# Lemming2_power.net
KiCad netlist of a schematic drawn in EAGLE
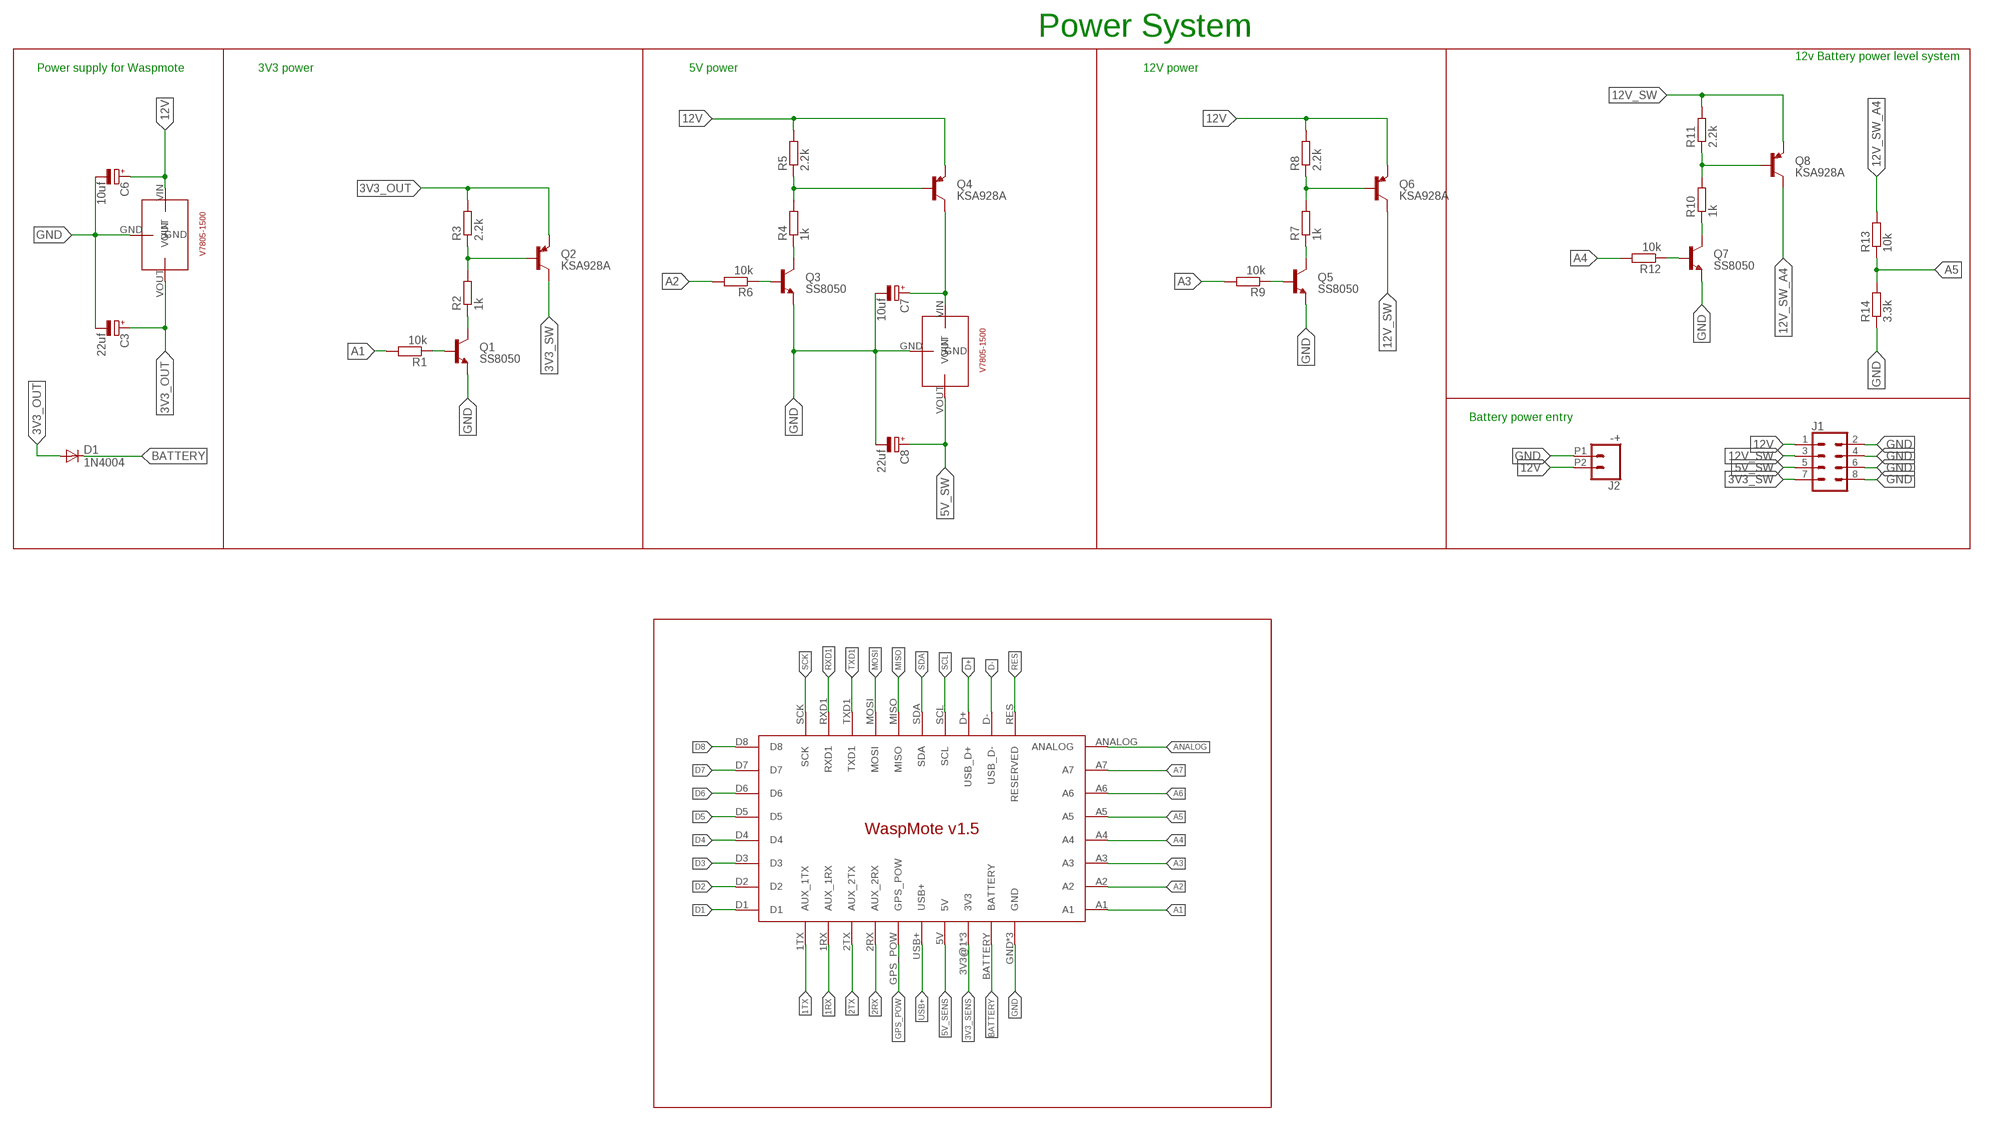
[diagram p0: schematic, sheet 1]

(export (version "E")
  (design (tool "Eeschema 10.0.6"))
  (components
    (comp (ref "C3")
      (value "22uf")
      (footprint "eagle-import:E2,5-5")
      (libsource (lib "eagle-import") (part "CPOL-EUE2.5-5"))
    )
    (comp (ref "C6")
      (value "10uf")
      (footprint "eagle-import:E2,5-5")
      (libsource (lib "eagle-import") (part "CPOL-EUE2.5-5"))
    )
    (comp (ref "C7")
      (value "10uf")
      (footprint "eagle-import:E2,5-5")
      (libsource (lib "eagle-import") (part "CPOL-EUE2.5-5"))
    )
    (comp (ref "C8")
      (value "22uf")
      (footprint "eagle-import:E2,5-5")
      (libsource (lib "eagle-import") (part "CPOL-EUE2.5-5"))
    )
    (comp (ref "D1")
      (value "1N4004")
      (footprint "eagle-import:DO41-10")
      (libsource (lib "eagle-import") (part "1N4004"))
    )
    (comp (ref "J1")
      (value "CONN_04X2")
      (footprint "eagle-import:2X4")
      (libsource (lib "eagle-import") (part "CONN_04X2"))
    )
    (comp (ref "J2")
      (value "-+")
      (footprint "eagle-import:1X02_2.54_SCREWTERM")
      (libsource (lib "eagle-import") (part "CONN_022.54MM_SCREWTERM"))
    )
    (comp (ref "LM7805")
      (value "V7805-1500")
      (footprint "eagle-import:V7805-1500")
      (libsource (lib "eagle-import") (part "V7805-1500"))
    )
    (comp (ref "Q1")
      (value "SS8050")
      (footprint "eagle-import:TO-92-EBC")
      (libsource (lib "eagle-import") (part "SS8050"))
    )
    (comp (ref "Q2")
      (value "KSA928A")
      (footprint "eagle-import:TO-92-ECB")
      (libsource (lib "eagle-import") (part "KSA928A"))
    )
    (comp (ref "Q3")
      (value "SS8050")
      (footprint "eagle-import:TO-92-EBC")
      (libsource (lib "eagle-import") (part "SS8050"))
    )
    (comp (ref "Q4")
      (value "KSA928A")
      (footprint "eagle-import:TO-92-ECB")
      (libsource (lib "eagle-import") (part "KSA928A"))
    )
    (comp (ref "Q5")
      (value "SS8050")
      (footprint "eagle-import:TO-92-EBC")
      (libsource (lib "eagle-import") (part "SS8050"))
    )
    (comp (ref "Q6")
      (value "KSA928A")
      (footprint "eagle-import:TO-92-ECB")
      (libsource (lib "eagle-import") (part "KSA928A"))
    )
    (comp (ref "Q7")
      (value "SS8050")
      (footprint "eagle-import:TO-92-EBC")
      (libsource (lib "eagle-import") (part "SS8050"))
    )
    (comp (ref "Q8")
      (value "KSA928A")
      (footprint "eagle-import:TO-92-ECB")
      (libsource (lib "eagle-import") (part "KSA928A"))
    )
    (comp (ref "R1")
      (value "10k")
      (footprint "eagle-import:RESISTOR_0309_10")
      (libsource (lib "eagle-import") (part "RESISTOR_R-EU_0309/10"))
    )
    (comp (ref "R2")
      (value "1k")
      (footprint "eagle-import:RESISTOR_0309_10")
      (libsource (lib "eagle-import") (part "RESISTOR_R-EU_0309/10"))
    )
    (comp (ref "R3")
      (value "2.2k")
      (footprint "eagle-import:RESISTOR_0309_10")
      (libsource (lib "eagle-import") (part "RESISTOR_R-EU_0309/10"))
    )
    (comp (ref "R4")
      (value "1k")
      (footprint "eagle-import:RESISTOR_0309_10")
      (libsource (lib "eagle-import") (part "RESISTOR_R-EU_0309/10"))
    )
    (comp (ref "R5")
      (value "2.2k")
      (footprint "eagle-import:RESISTOR_0309_10")
      (libsource (lib "eagle-import") (part "RESISTOR_R-EU_0309/10"))
    )
    (comp (ref "R6")
      (value "10k")
      (footprint "eagle-import:RESISTOR_0309_10")
      (libsource (lib "eagle-import") (part "RESISTOR_R-EU_0309/10"))
    )
    (comp (ref "R7")
      (value "1k")
      (footprint "eagle-import:RESISTOR_0309_10")
      (libsource (lib "eagle-import") (part "RESISTOR_R-EU_0309/10"))
    )
    (comp (ref "R8")
      (value "2.2k")
      (footprint "eagle-import:RESISTOR_0309_10")
      (libsource (lib "eagle-import") (part "RESISTOR_R-EU_0309/10"))
    )
    (comp (ref "R9")
      (value "10k")
      (footprint "eagle-import:RESISTOR_0309_10")
      (libsource (lib "eagle-import") (part "RESISTOR_R-EU_0309/10"))
    )
    (comp (ref "R10")
      (value "1k")
      (footprint "eagle-import:RESISTOR_0309_10")
      (libsource (lib "eagle-import") (part "RESISTOR_R-EU_0309/10"))
    )
    (comp (ref "R11")
      (value "2.2k")
      (footprint "eagle-import:RESISTOR_0309_10")
      (libsource (lib "eagle-import") (part "RESISTOR_R-EU_0309/10"))
    )
    (comp (ref "R12")
      (value "10k")
      (footprint "eagle-import:RESISTOR_0309_10")
      (libsource (lib "eagle-import") (part "RESISTOR_R-EU_0309/10"))
    )
    (comp (ref "R13")
      (value "10k")
      (footprint "eagle-import:RESISTOR_0309_10")
      (libsource (lib "eagle-import") (part "RESISTOR_R-EU_0309/10"))
    )
    (comp (ref "R14")
      (value "3.3k")
      (footprint "eagle-import:RESISTOR_0309_10")
      (libsource (lib "eagle-import") (part "RESISTOR_R-EU_0309/10"))
    )
    (comp (ref "U$1")
      (value "WASPMOTE_V1.5")
      (footprint "eagle-import:WASPMOTE_V1.5")
      (libsource (lib "eagle-import") (part "WASPMOTE_V1.5"))
    )
    (comp (ref "U$22")
      (value "V7803-1500")
      (footprint "eagle-import:V7805-1500")
      (libsource (lib "eagle-import") (part "V7805-1500"))
    )
  )
  (nets
    (net (code "1") (name "1RX") (class "Default")
      (node (ref "U$1") (pin "1RX") (pinfunction "AUX_1RX_1RX") (pintype "bidirectional"))
    )
    (net (code "2") (name "1TX") (class "Default")
      (node (ref "U$1") (pin "1TX") (pinfunction "AUX_1TX_1TX") (pintype "bidirectional"))
    )
    (net (code "3") (name "2RX") (class "Default")
      (node (ref "U$1") (pin "2RX") (pinfunction "AUX_2RX_2RX") (pintype "bidirectional"))
    )
    (net (code "4") (name "2TX") (class "Default")
      (node (ref "U$1") (pin "2TX") (pinfunction "AUX_2TX_2TX") (pintype "bidirectional"))
    )
    (net (code "5") (name "3V3_OUT") (class "Default")
      (node (ref "C3") (pin "+") (pinfunction "+_+") (pintype "passive"))
      (node (ref "D1") (pin "A") (pinfunction "A_A") (pintype "passive"))
      (node (ref "Q2") (pin "E") (pinfunction "E_E") (pintype "passive"))
      (node (ref "R3") (pin "2") (pinfunction "2_2") (pintype "passive"))
      (node (ref "U$22") (pin "VOUT") (pinfunction "VOUT_VOUT") (pintype "bidirectional"))
    )
    (net (code "6") (name "3V3_SENS") (class "Default")
      (node (ref "U$1") (pin "3V3@1") (pinfunction "3V3_3V3@1") (pintype "bidirectional"))
      (node (ref "U$1") (pin "3V3@2") (pinfunction "3V3_3V3@2") (pintype "bidirectional"))
      (node (ref "U$1") (pin "3V3@3") (pinfunction "3V3_3V3@3") (pintype "bidirectional"))
    )
    (net (code "7") (name "3V3_SW") (class "Default")
      (node (ref "J1") (pin "7") (pinfunction "7_7") (pintype "passive"))
      (node (ref "Q2") (pin "C") (pinfunction "C_C") (pintype "passive"))
    )
    (net (code "8") (name "5V_SENS") (class "Default")
      (node (ref "U$1") (pin "5V") (pinfunction "5V_5V") (pintype "bidirectional"))
    )
    (net (code "9") (name "5V_SW") (class "Default")
      (node (ref "C8") (pin "+") (pinfunction "+_+") (pintype "passive"))
      (node (ref "J1") (pin "5") (pinfunction "5_5") (pintype "passive"))
      (node (ref "LM7805") (pin "VOUT") (pinfunction "VOUT_VOUT") (pintype "bidirectional"))
    )
    (net (code "10") (name "12V") (class "Default")
      (node (ref "C6") (pin "+") (pinfunction "+_+") (pintype "passive"))
      (node (ref "J1") (pin "1") (pinfunction "1_1") (pintype "passive"))
      (node (ref "J2") (pin "P2") (pinfunction "2_P2") (pintype "passive"))
      (node (ref "Q4") (pin "E") (pinfunction "E_E") (pintype "passive"))
      (node (ref "Q6") (pin "E") (pinfunction "E_E") (pintype "passive"))
      (node (ref "R5") (pin "2") (pinfunction "2_2") (pintype "passive"))
      (node (ref "R8") (pin "2") (pinfunction "2_2") (pintype "passive"))
      (node (ref "U$22") (pin "VIN") (pinfunction "VIN_VIN") (pintype "bidirectional"))
    )
    (net (code "11") (name "12V_SW") (class "Default")
      (node (ref "J1") (pin "3") (pinfunction "3_3") (pintype "passive"))
      (node (ref "Q6") (pin "C") (pinfunction "C_C") (pintype "passive"))
      (node (ref "Q8") (pin "E") (pinfunction "E_E") (pintype "passive"))
      (node (ref "R11") (pin "2") (pinfunction "2_2") (pintype "passive"))
    )
    (net (code "12") (name "12V_SW_A4") (class "Default")
      (node (ref "Q8") (pin "C") (pinfunction "C_C") (pintype "passive"))
      (node (ref "R13") (pin "2") (pinfunction "2_2") (pintype "passive"))
    )
    (net (code "13") (name "A1") (class "Default")
      (node (ref "R1") (pin "2") (pinfunction "2_2") (pintype "passive"))
      (node (ref "U$1") (pin "A1") (pinfunction "A1_A1") (pintype "bidirectional"))
    )
    (net (code "14") (name "A2") (class "Default")
      (node (ref "R6") (pin "2") (pinfunction "2_2") (pintype "passive"))
      (node (ref "U$1") (pin "A2") (pinfunction "A2_A2") (pintype "bidirectional"))
    )
    (net (code "15") (name "A3") (class "Default")
      (node (ref "R9") (pin "2") (pinfunction "2_2") (pintype "passive"))
      (node (ref "U$1") (pin "A3") (pinfunction "A3_A3") (pintype "bidirectional"))
    )
    (net (code "16") (name "A4") (class "Default")
      (node (ref "R12") (pin "2") (pinfunction "2_2") (pintype "passive"))
      (node (ref "U$1") (pin "A4") (pinfunction "A4_A4") (pintype "bidirectional"))
    )
    (net (code "17") (name "A5") (class "Default")
      (node (ref "R13") (pin "1") (pinfunction "1_1") (pintype "passive"))
      (node (ref "R14") (pin "2") (pinfunction "2_2") (pintype "passive"))
      (node (ref "U$1") (pin "A5") (pinfunction "A5_A5") (pintype "bidirectional"))
    )
    (net (code "18") (name "A6") (class "Default")
      (node (ref "U$1") (pin "A6") (pinfunction "A6_A6") (pintype "bidirectional"))
    )
    (net (code "19") (name "A7") (class "Default")
      (node (ref "U$1") (pin "A7") (pinfunction "A7_A7") (pintype "bidirectional"))
    )
    (net (code "20") (name "ANALOG") (class "Default")
      (node (ref "U$1") (pin "ANALOG") (pinfunction "ANALOG_ANALOG") (pintype "bidirectional"))
    )
    (net (code "21") (name "BATTERY") (class "Default")
      (node (ref "D1") (pin "C") (pinfunction "C_C") (pintype "passive"))
      (node (ref "U$1") (pin "BATTERY") (pinfunction "BATTERY_BATTERY") (pintype "bidirectional"))
    )
    (net (code "22") (name "D+") (class "Default")
      (node (ref "U$1") (pin "D+") (pinfunction "USB_D+_D+") (pintype "bidirectional"))
    )
    (net (code "23") (name "D-") (class "Default")
      (node (ref "U$1") (pin "D-") (pinfunction "USB_D-_D-") (pintype "bidirectional"))
    )
    (net (code "24") (name "D1") (class "Default")
      (node (ref "U$1") (pin "D1") (pinfunction "D1_D1") (pintype "bidirectional"))
    )
    (net (code "25") (name "D2") (class "Default")
      (node (ref "U$1") (pin "D2") (pinfunction "D2_D2") (pintype "bidirectional"))
    )
    (net (code "26") (name "D3") (class "Default")
      (node (ref "U$1") (pin "D3") (pinfunction "D3_D3") (pintype "bidirectional"))
    )
    (net (code "27") (name "D4") (class "Default")
      (node (ref "U$1") (pin "D4") (pinfunction "D4_D4") (pintype "bidirectional"))
    )
    (net (code "28") (name "D5") (class "Default")
      (node (ref "U$1") (pin "D5") (pinfunction "D5_D5") (pintype "bidirectional"))
    )
    (net (code "29") (name "D6") (class "Default")
      (node (ref "U$1") (pin "D6") (pinfunction "D6_D6") (pintype "bidirectional"))
    )
    (net (code "30") (name "D7") (class "Default")
      (node (ref "U$1") (pin "D7") (pinfunction "D7_D7") (pintype "bidirectional"))
    )
    (net (code "31") (name "D8") (class "Default")
      (node (ref "U$1") (pin "D8") (pinfunction "D8_D8") (pintype "bidirectional"))
    )
    (net (code "32") (name "GND") (class "Default")
      (node (ref "C3") (pin "-") (pinfunction "-_-") (pintype "passive"))
      (node (ref "C6") (pin "-") (pinfunction "-_-") (pintype "passive"))
      (node (ref "C7") (pin "-") (pinfunction "-_-") (pintype "passive"))
      (node (ref "C8") (pin "-") (pinfunction "-_-") (pintype "passive"))
      (node (ref "J1") (pin "2") (pinfunction "2_2") (pintype "passive"))
      (node (ref "J1") (pin "4") (pinfunction "4_4") (pintype "passive"))
      (node (ref "J1") (pin "6") (pinfunction "6_6") (pintype "passive"))
      (node (ref "J1") (pin "8") (pinfunction "8_8") (pintype "passive"))
      (node (ref "J2") (pin "P1") (pinfunction "1_P1") (pintype "passive"))
      (node (ref "LM7805") (pin "GND") (pinfunction "GND_GND") (pintype "bidirectional"))
      (node (ref "Q1") (pin "E") (pinfunction "E_E") (pintype "passive"))
      (node (ref "Q3") (pin "E") (pinfunction "E_E") (pintype "passive"))
      (node (ref "Q5") (pin "E") (pinfunction "E_E") (pintype "passive"))
      (node (ref "Q7") (pin "E") (pinfunction "E_E") (pintype "passive"))
      (node (ref "R14") (pin "1") (pinfunction "1_1") (pintype "passive"))
      (node (ref "U$1") (pin "GND") (pinfunction "GND_GND") (pintype "bidirectional"))
      (node (ref "U$1") (pin "GND_2") (pinfunction "GND_GND_2") (pintype "bidirectional"))
      (node (ref "U$1") (pin "USB-") (pinfunction "GND_USB-") (pintype "bidirectional"))
      (node (ref "U$22") (pin "GND") (pinfunction "GND_GND") (pintype "bidirectional"))
    )
    (net (code "33") (name "GPS_POW") (class "Default")
      (node (ref "U$1") (pin "GPS_POW") (pinfunction "GPS_POW_GPS_POW") (pintype "bidirectional"))
    )
    (net (code "34") (name "MISO") (class "Default")
      (node (ref "U$1") (pin "MISO") (pinfunction "MISO_MISO") (pintype "bidirectional"))
    )
    (net (code "35") (name "MOSI") (class "Default")
      (node (ref "U$1") (pin "MOSI") (pinfunction "MOSI_MOSI") (pintype "bidirectional"))
    )
    (net (code "36") (name "Net-(C7-Pad+)") (class "Default")
      (node (ref "C7") (pin "+") (pinfunction "+_+") (pintype "passive"))
      (node (ref "LM7805") (pin "VIN") (pinfunction "VIN_VIN") (pintype "bidirectional"))
      (node (ref "Q4") (pin "C") (pinfunction "C_C") (pintype "passive"))
    )
    (net (code "37") (name "Net-(Q1-PadB)") (class "Default")
      (node (ref "Q1") (pin "B") (pinfunction "B_B") (pintype "passive"))
      (node (ref "R1") (pin "1") (pinfunction "1_1") (pintype "passive"))
    )
    (net (code "38") (name "Net-(Q1-PadC)") (class "Default")
      (node (ref "Q1") (pin "C") (pinfunction "C_C") (pintype "passive"))
      (node (ref "R2") (pin "1") (pinfunction "1_1") (pintype "passive"))
    )
    (net (code "39") (name "Net-(Q2-PadB)") (class "Default")
      (node (ref "Q2") (pin "B") (pinfunction "B_B") (pintype "passive"))
      (node (ref "R2") (pin "2") (pinfunction "2_2") (pintype "passive"))
      (node (ref "R3") (pin "1") (pinfunction "1_1") (pintype "passive"))
    )
    (net (code "40") (name "Net-(Q3-PadB)") (class "Default")
      (node (ref "Q3") (pin "B") (pinfunction "B_B") (pintype "passive"))
      (node (ref "R6") (pin "1") (pinfunction "1_1") (pintype "passive"))
    )
    (net (code "41") (name "Net-(Q3-PadC)") (class "Default")
      (node (ref "Q3") (pin "C") (pinfunction "C_C") (pintype "passive"))
      (node (ref "R4") (pin "1") (pinfunction "1_1") (pintype "passive"))
    )
    (net (code "42") (name "Net-(Q4-PadB)") (class "Default")
      (node (ref "Q4") (pin "B") (pinfunction "B_B") (pintype "passive"))
      (node (ref "R4") (pin "2") (pinfunction "2_2") (pintype "passive"))
      (node (ref "R5") (pin "1") (pinfunction "1_1") (pintype "passive"))
    )
    (net (code "43") (name "Net-(Q5-PadB)") (class "Default")
      (node (ref "Q5") (pin "B") (pinfunction "B_B") (pintype "passive"))
      (node (ref "R9") (pin "1") (pinfunction "1_1") (pintype "passive"))
    )
    (net (code "44") (name "Net-(Q5-PadC)") (class "Default")
      (node (ref "Q5") (pin "C") (pinfunction "C_C") (pintype "passive"))
      (node (ref "R7") (pin "1") (pinfunction "1_1") (pintype "passive"))
    )
    (net (code "45") (name "Net-(Q6-PadB)") (class "Default")
      (node (ref "Q6") (pin "B") (pinfunction "B_B") (pintype "passive"))
      (node (ref "R7") (pin "2") (pinfunction "2_2") (pintype "passive"))
      (node (ref "R8") (pin "1") (pinfunction "1_1") (pintype "passive"))
    )
    (net (code "46") (name "Net-(Q7-PadB)") (class "Default")
      (node (ref "Q7") (pin "B") (pinfunction "B_B") (pintype "passive"))
      (node (ref "R12") (pin "1") (pinfunction "1_1") (pintype "passive"))
    )
    (net (code "47") (name "Net-(Q7-PadC)") (class "Default")
      (node (ref "Q7") (pin "C") (pinfunction "C_C") (pintype "passive"))
      (node (ref "R10") (pin "1") (pinfunction "1_1") (pintype "passive"))
    )
    (net (code "48") (name "Net-(Q8-PadB)") (class "Default")
      (node (ref "Q8") (pin "B") (pinfunction "B_B") (pintype "passive"))
      (node (ref "R10") (pin "2") (pinfunction "2_2") (pintype "passive"))
      (node (ref "R11") (pin "1") (pinfunction "1_1") (pintype "passive"))
    )
    (net (code "49") (name "RES") (class "Default")
      (node (ref "U$1") (pin "RES") (pinfunction "RESERVED_RES") (pintype "bidirectional"))
    )
    (net (code "50") (name "RXD1") (class "Default")
      (node (ref "U$1") (pin "RXD1") (pinfunction "RXD1_RXD1") (pintype "bidirectional"))
    )
    (net (code "51") (name "SCK") (class "Default")
      (node (ref "U$1") (pin "SCK") (pinfunction "SCK_SCK") (pintype "bidirectional"))
    )
    (net (code "52") (name "SCL") (class "Default")
      (node (ref "U$1") (pin "SCL") (pinfunction "SCL_SCL") (pintype "bidirectional"))
    )
    (net (code "53") (name "SDA") (class "Default")
      (node (ref "U$1") (pin "SDA") (pinfunction "SDA_SDA") (pintype "bidirectional"))
    )
    (net (code "54") (name "TXD1") (class "Default")
      (node (ref "U$1") (pin "TXD1") (pinfunction "TXD1_TXD1") (pintype "bidirectional"))
    )
    (net (code "55") (name "USB+") (class "Default")
      (node (ref "U$1") (pin "USB+") (pinfunction "USB+_USB+") (pintype "bidirectional"))
    )
  )
)
